# V1.net
KiCad netlist of a schematic drawn in EAGLE
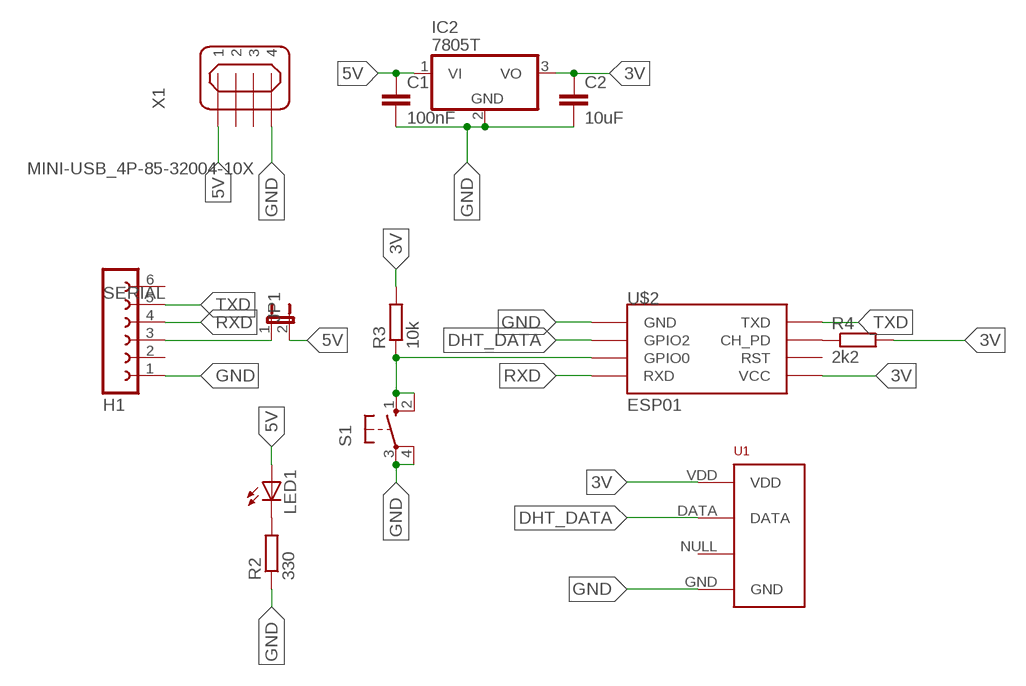
[diagram p0: schematic, sheet 1]

(export (version "E")
  (design (tool "Eeschema 10.0.6"))
  (components
    (comp (ref "C1")
      (value "100nF")
      (footprint "eagle-import:C025-030X050")
      (libsource (lib "eagle-import") (part "C-EU025-030X050"))
    )
    (comp (ref "C2")
      (value "10uF")
      (footprint "eagle-import:C025-030X050")
      (libsource (lib "eagle-import") (part "C-EU025-030X050"))
    )
    (comp (ref "IC2")
      (value "7805T")
      (footprint "eagle-import:TO220H")
      (libsource (lib "eagle-import") (part "78T05"))
    )
    (comp (ref "JP1")
      (value "JP1E")
      (footprint "eagle-import:JP1")
      (libsource (lib "eagle-import") (part "JP1E"))
    )
    (comp (ref "LED1")
      (value "LED5MM")
      (footprint "eagle-import:LED5MM")
      (libsource (lib "eagle-import") (part "LED5MM"))
    )
    (comp (ref "R2")
      (value "330")
      (footprint "eagle-import:0207_10")
      (libsource (lib "eagle-import") (part "R-EU_0207/10"))
    )
    (comp (ref "R3")
      (value "10k")
      (footprint "eagle-import:0207_10")
      (libsource (lib "eagle-import") (part "R-EU_0207/10"))
    )
    (comp (ref "R4")
      (value "2k2")
      (footprint "eagle-import:0207_10")
      (libsource (lib "eagle-import") (part "R-EU_0207/10"))
    )
    (comp (ref "S1")
      (value "10-XX")
      (footprint "eagle-import:B3F-10XX")
      (fields (field (name "MPN") "B3F-1000"))
      (libsource (lib "eagle-import") (part "10-XX"))
    )
    (comp (ref "SERIAL")
      (value "H1")
      (footprint "eagle-import:FE06")
      (libsource (lib "eagle-import") (part "FE06-1"))
    )
    (comp (ref "U$2")
      (value "ESP01")
      (footprint "eagle-import:ESP01")
      (libsource (lib "eagle-import") (part "ESP01"))
    )
    (comp (ref "U1")
      (value "RHT03_DHT-22_AM2302")
      (footprint "eagle-import:RHT03_DHT-22")
      (libsource (lib "eagle-import") (part "RHT03_DHT-22_AM2302"))
    )
    (comp (ref "X1")
      (value "MINI-USB_4P-85-32004-10X")
      (footprint "eagle-import:85-32004-10X")
      (libsource (lib "eagle-import") (part "MINI-USB_4P-85-32004-10X"))
    )
  )
  (nets
    (net (code "1") (name "3V") (class "Default")
      (node (ref "C2") (pin "1") (pinfunction "1_1") (pintype "passive"))
      (node (ref "IC2") (pin "3") (pinfunction "VO_3") (pintype "passive"))
      (node (ref "R3") (pin "2") (pinfunction "2_2") (pintype "passive"))
      (node (ref "R4") (pin "2") (pinfunction "2_2") (pintype "passive"))
      (node (ref "U$2") (pin "VCC") (pinfunction "VCC_VCC") (pintype "bidirectional"))
      (node (ref "U1") (pin "VDD") (pinfunction "VDD_VDD") (pintype "power_in"))
    )
    (net (code "2") (name "5V") (class "Default")
      (node (ref "C1") (pin "1") (pinfunction "1_1") (pintype "passive"))
      (node (ref "IC2") (pin "1") (pinfunction "VI_1") (pintype "input"))
      (node (ref "JP1") (pin "2") (pinfunction "2_2") (pintype "passive"))
      (node (ref "LED1") (pin "A") (pinfunction "A_A") (pintype "passive"))
      (node (ref "X1") (pin "1") (pinfunction "1_1") (pintype "passive"))
    )
    (net (code "3") (name "DHT_DATA") (class "Default")
      (node (ref "U$2") (pin "GPIO2") (pinfunction "GPIO2_GPIO2") (pintype "bidirectional"))
      (node (ref "U1") (pin "DATA") (pinfunction "DATA_DATA") (pintype "bidirectional"))
    )
    (net (code "4") (name "GND") (class "Default")
      (node (ref "C1") (pin "2") (pinfunction "2_2") (pintype "passive"))
      (node (ref "C2") (pin "2") (pinfunction "2_2") (pintype "passive"))
      (node (ref "IC2") (pin "2") (pinfunction "GND_2") (pintype "passive"))
      (node (ref "R2") (pin "1") (pinfunction "1_1") (pintype "passive"))
      (node (ref "S1") (pin "3") (pinfunction "P_3") (pintype "passive"))
      (node (ref "S1") (pin "4") (pinfunction "P1_4") (pintype "passive"))
      (node (ref "SERIAL") (pin "1") (pinfunction "1_1") (pintype "passive"))
      (node (ref "U$2") (pin "GND") (pinfunction "GND_GND") (pintype "bidirectional"))
      (node (ref "U1") (pin "GND") (pinfunction "GND_GND") (pintype "power_in"))
      (node (ref "X1") (pin "4") (pinfunction "4_4") (pintype "passive"))
    )
    (net (code "5") (name "Net-(JP1-Pad1)") (class "Default")
      (node (ref "JP1") (pin "1") (pinfunction "1_1") (pintype "passive"))
      (node (ref "SERIAL") (pin "3") (pinfunction "3_3") (pintype "passive"))
    )
    (net (code "6") (name "Net-(LED1-C)") (class "Default")
      (node (ref "LED1") (pin "K") (pinfunction "C_K") (pintype "passive"))
      (node (ref "R2") (pin "2") (pinfunction "2_2") (pintype "passive"))
    )
    (net (code "7") (name "Net-(R4-Pad1)") (class "Default")
      (node (ref "R4") (pin "1") (pinfunction "1_1") (pintype "passive"))
      (node (ref "U$2") (pin "CH_PD") (pinfunction "CH_PD_CH_PD") (pintype "bidirectional"))
    )
    (net (code "8") (name "Net-(S1-S)") (class "Default")
      (node (ref "R3") (pin "1") (pinfunction "1_1") (pintype "passive"))
      (node (ref "S1") (pin "1") (pinfunction "S_1") (pintype "passive"))
      (node (ref "S1") (pin "2") (pinfunction "S1_2") (pintype "passive"))
      (node (ref "U$2") (pin "GPIO0") (pinfunction "GPIO0_GPIO0") (pintype "bidirectional"))
    )
    (net (code "9") (name "RXD") (class "Default")
      (node (ref "SERIAL") (pin "4") (pinfunction "4_4") (pintype "passive"))
      (node (ref "U$2") (pin "RX") (pinfunction "RXD_RX") (pintype "bidirectional"))
    )
    (net (code "10") (name "TXD") (class "Default")
      (node (ref "SERIAL") (pin "5") (pinfunction "5_5") (pintype "passive"))
      (node (ref "U$2") (pin "TX") (pinfunction "TXD_TX") (pintype "bidirectional"))
    )
    (net (code "11") (name "unconnected-(SERIAL-Pad2)") (class "Default")
      (node (ref "SERIAL") (pin "2") (pinfunction "2_2") (pintype "passive"))
    )
    (net (code "12") (name "unconnected-(SERIAL-Pad6)") (class "Default")
      (node (ref "SERIAL") (pin "6") (pinfunction "6_6") (pintype "passive"))
    )
    (net (code "13") (name "unconnected-(U$2-PadRST)") (class "Default")
      (node (ref "U$2") (pin "RST") (pinfunction "RST_RST") (pintype "bidirectional"))
    )
    (net (code "14") (name "unconnected-(U1-PadNULL)") (class "Default")
      (node (ref "U1") (pin "NULL") (pinfunction "NULL_NULL") (pintype "no_connect"))
    )
    (net (code "15") (name "unconnected-(X1-Pad2)") (class "Default")
      (node (ref "X1") (pin "2") (pinfunction "2_2") (pintype "passive"))
    )
    (net (code "16") (name "unconnected-(X1-Pad3)") (class "Default")
      (node (ref "X1") (pin "3") (pinfunction "3_3") (pintype "passive"))
    )
  )
)
